# lab4_schematic.net
KiCad netlist of a schematic drawn in Altium Designer
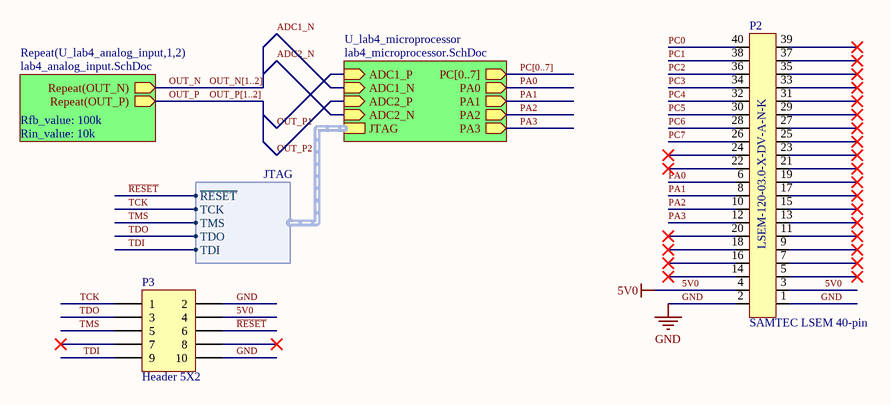
[diagram p0: lab4_schematic.SchDoc]

(export (version "E")
  (design (tool "Eeschema 10.0.6"))
  (components
    (comp (ref "P2")
      (value "SAMTEC LSEM 40-pin")
      (footprint "PcbLib_MW:LSEM-120-03.0-L-DV-A-N-K-TR")
      (fields (field (name "MANUFACTURER") "SAMTEC") (field (name "PART NUMBER") "LSEM-120-03.0-X-DV-A-N-K"))
      (libsource (lib "Schlib_MW") (part "LSEM-120-03.0-X-DV-A-N-K"))
    )
    (comp (ref "P3")
      (value "Header 5X2")
      (footprint "HDR2X5")
      (description "Header, 5-Pin, Dual row")
      (fields (field (name "PUBLISHER") "Altium Limited"))
      (libsource (lib "Miscellaneous Connectors") (part "Header 5X2"))
    )
  )
  (nets
    (net (code "12") (name "/PA0") (class "Default")
      (node (ref "P2") (pin "6") (pinfunction "4_6") (pintype "passive"))
    )
    (net (code "13") (name "/PA1") (class "Default")
      (node (ref "P2") (pin "8") (pinfunction "5_8") (pintype "passive"))
    )
    (net (code "14") (name "/PA2") (class "Default")
      (node (ref "P2") (pin "10") (pinfunction "6_10") (pintype "passive"))
    )
    (net (code "15") (name "/PA3") (class "Default")
      (node (ref "P2") (pin "12") (pinfunction "7_12") (pintype "passive"))
    )
    (net (code "16") (name "/PC0") (class "Default")
      (node (ref "P2") (pin "40") (pinfunction "21_40") (pintype "passive"))
    )
    (net (code "17") (name "/PC1") (class "Default")
      (node (ref "P2") (pin "38") (pinfunction "20_38") (pintype "passive"))
    )
    (net (code "18") (name "/PC2") (class "Default")
      (node (ref "P2") (pin "36") (pinfunction "19_36") (pintype "passive"))
    )
    (net (code "19") (name "/PC3") (class "Default")
      (node (ref "P2") (pin "34") (pinfunction "18_34") (pintype "passive"))
    )
    (net (code "20") (name "/PC4") (class "Default")
      (node (ref "P2") (pin "32") (pinfunction "17_32") (pintype "passive"))
    )
    (net (code "21") (name "/PC5") (class "Default")
      (node (ref "P2") (pin "30") (pinfunction "16_30") (pintype "passive"))
    )
    (net (code "22") (name "/PC6") (class "Default")
      (node (ref "P2") (pin "28") (pinfunction "15_28") (pintype "passive"))
    )
    (net (code "23") (name "/PC7") (class "Default")
      (node (ref "P2") (pin "26") (pinfunction "14_26") (pintype "passive"))
    )
    (net (code "25") (name "/TCK") (class "Default")
      (node (ref "P3") (pin "1") (pinfunction "1_1") (pintype "passive"))
    )
    (net (code "26") (name "/TDI") (class "Default")
      (node (ref "P3") (pin "9") (pinfunction "9_9") (pintype "passive"))
    )
    (net (code "27") (name "/TDO") (class "Default")
      (node (ref "P3") (pin "3") (pinfunction "3_3") (pintype "passive"))
    )
    (net (code "28") (name "/TMS") (class "Default")
      (node (ref "P3") (pin "5") (pinfunction "5_5") (pintype "passive"))
    )
    (net (code "30") (name "/~{RESET}") (class "Default")
      (node (ref "P3") (pin "6") (pinfunction "6_6") (pintype "passive"))
    )
    (net (code "31") (name "5V0") (class "Default")
      (node (ref "P2") (pin "3") (pinfunction "2_3") (pintype "passive"))
      (node (ref "P2") (pin "4") (pinfunction "3_4") (pintype "passive"))
      (node (ref "P3") (pin "4") (pinfunction "4_4") (pintype "passive"))
    )
    (net (code "32") (name "GND") (class "Default")
      (node (ref "P2") (pin "1") (pinfunction "1_1") (pintype "passive"))
      (node (ref "P2") (pin "2") (pinfunction "2_2") (pintype "passive"))
      (node (ref "P3") (pin "10") (pinfunction "10_10") (pintype "passive"))
      (node (ref "P3") (pin "2") (pinfunction "2_2") (pintype "passive"))
    )
    (net (code "33") (name "unconnected-(P2-3-Pad5)") (class "Default")
      (node (ref "P2") (pin "5") (pinfunction "3_5") (pintype "passive+no_connect"))
    )
    (net (code "34") (name "unconnected-(P2-4-Pad7)") (class "Default")
      (node (ref "P2") (pin "7") (pinfunction "4_7") (pintype "passive+no_connect"))
    )
    (net (code "35") (name "unconnected-(P2-5-Pad9)") (class "Default")
      (node (ref "P2") (pin "9") (pinfunction "5_9") (pintype "passive+no_connect"))
    )
    (net (code "36") (name "unconnected-(P2-6-Pad11)") (class "Default")
      (node (ref "P2") (pin "11") (pinfunction "6_11") (pintype "passive+no_connect"))
    )
    (net (code "37") (name "unconnected-(P2-7-Pad13)") (class "Default")
      (node (ref "P2") (pin "13") (pinfunction "7_13") (pintype "passive+no_connect"))
    )
    (net (code "38") (name "unconnected-(P2-8-Pad14)") (class "Default")
      (node (ref "P2") (pin "14") (pinfunction "8_14") (pintype "passive+no_connect"))
    )
    (net (code "39") (name "unconnected-(P2-8-Pad15)") (class "Default")
      (node (ref "P2") (pin "15") (pinfunction "8_15") (pintype "passive+no_connect"))
    )
    (net (code "40") (name "unconnected-(P2-9-Pad16)") (class "Default")
      (node (ref "P2") (pin "16") (pinfunction "9_16") (pintype "passive+no_connect"))
    )
    (net (code "41") (name "unconnected-(P2-9-Pad17)") (class "Default")
      (node (ref "P2") (pin "17") (pinfunction "9_17") (pintype "passive+no_connect"))
    )
    (net (code "42") (name "unconnected-(P2-10-Pad18)") (class "Default")
      (node (ref "P2") (pin "18") (pinfunction "10_18") (pintype "passive+no_connect"))
    )
    (net (code "43") (name "unconnected-(P2-10-Pad19)") (class "Default")
      (node (ref "P2") (pin "19") (pinfunction "10_19") (pintype "passive+no_connect"))
    )
    (net (code "44") (name "unconnected-(P2-11-Pad20)") (class "Default")
      (node (ref "P2") (pin "20") (pinfunction "11_20") (pintype "passive+no_connect"))
    )
    (net (code "45") (name "unconnected-(P2-11-Pad21)") (class "Default")
      (node (ref "P2") (pin "21") (pinfunction "11_21") (pintype "passive+no_connect"))
    )
    (net (code "46") (name "unconnected-(P2-12-Pad22)") (class "Default")
      (node (ref "P2") (pin "22") (pinfunction "12_22") (pintype "passive+no_connect"))
    )
    (net (code "47") (name "unconnected-(P2-12-Pad23)") (class "Default")
      (node (ref "P2") (pin "23") (pinfunction "12_23") (pintype "passive+no_connect"))
    )
    (net (code "48") (name "unconnected-(P2-13-Pad24)") (class "Default")
      (node (ref "P2") (pin "24") (pinfunction "13_24") (pintype "passive+no_connect"))
    )
    (net (code "49") (name "unconnected-(P2-13-Pad25)") (class "Default")
      (node (ref "P2") (pin "25") (pinfunction "13_25") (pintype "passive+no_connect"))
    )
    (net (code "50") (name "unconnected-(P2-14-Pad27)") (class "Default")
      (node (ref "P2") (pin "27") (pinfunction "14_27") (pintype "passive+no_connect"))
    )
    (net (code "51") (name "unconnected-(P2-15-Pad29)") (class "Default")
      (node (ref "P2") (pin "29") (pinfunction "15_29") (pintype "passive+no_connect"))
    )
    (net (code "52") (name "unconnected-(P2-16-Pad31)") (class "Default")
      (node (ref "P2") (pin "31") (pinfunction "16_31") (pintype "passive+no_connect"))
    )
    (net (code "53") (name "unconnected-(P2-17-Pad33)") (class "Default")
      (node (ref "P2") (pin "33") (pinfunction "17_33") (pintype "passive+no_connect"))
    )
    (net (code "54") (name "unconnected-(P2-18-Pad35)") (class "Default")
      (node (ref "P2") (pin "35") (pinfunction "18_35") (pintype "passive+no_connect"))
    )
    (net (code "55") (name "unconnected-(P2-19-Pad37)") (class "Default")
      (node (ref "P2") (pin "37") (pinfunction "19_37") (pintype "passive+no_connect"))
    )
    (net (code "56") (name "unconnected-(P2-20-Pad39)") (class "Default")
      (node (ref "P2") (pin "39") (pinfunction "20_39") (pintype "passive+no_connect"))
    )
    (net (code "57") (name "unconnected-(P3-Pad7)") (class "Default")
      (node (ref "P3") (pin "7") (pinfunction "7_7") (pintype "passive+no_connect"))
    )
    (net (code "58") (name "unconnected-(P3-Pad8)") (class "Default")
      (node (ref "P3") (pin "8") (pinfunction "8_8") (pintype "passive+no_connect"))
    )
  )
)
